# pcb_main.net
KiCad netlist of a schematic drawn in EAGLE
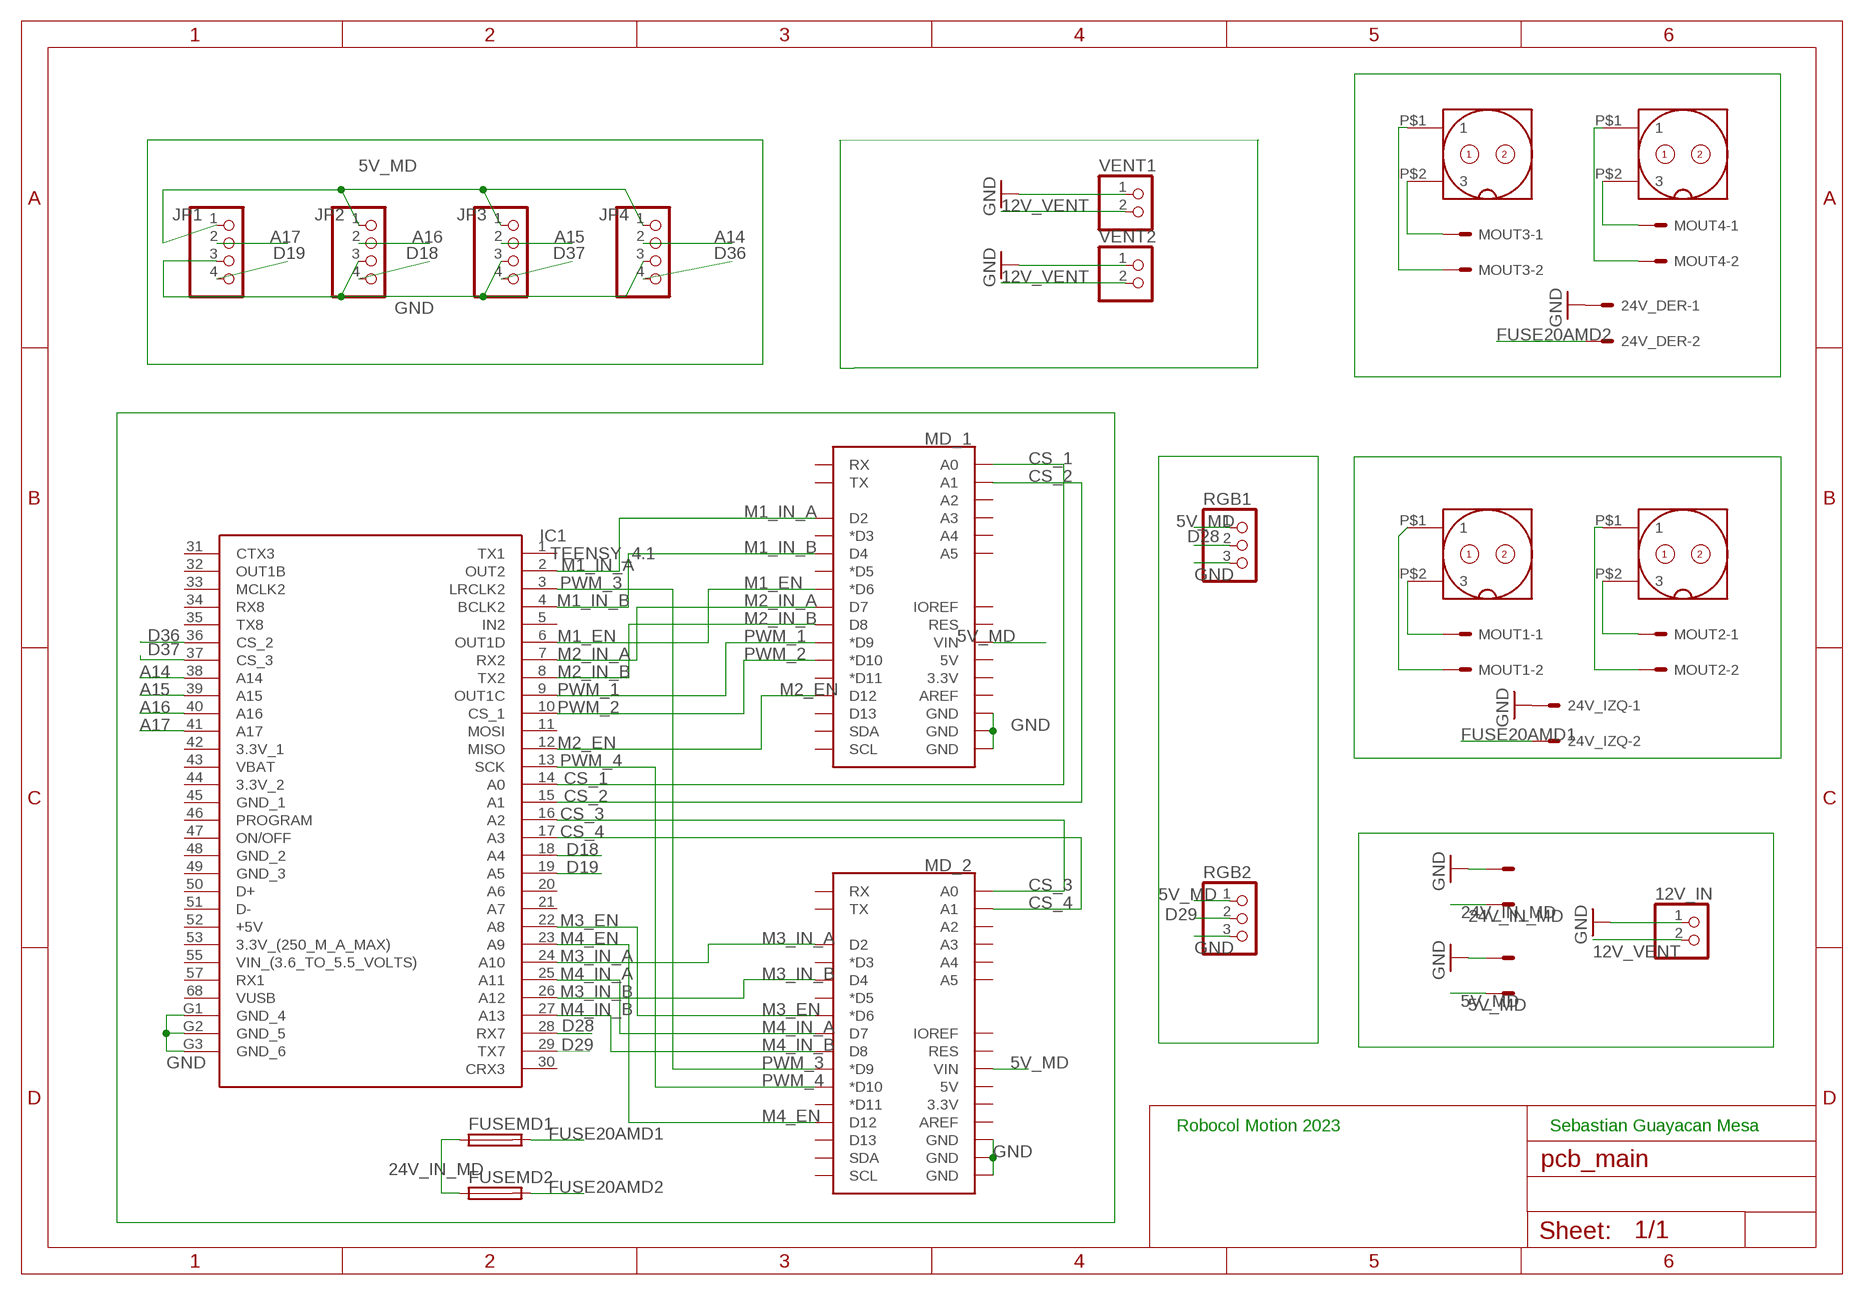
[diagram p0: schematic, sheet 1]

(export (version "E")
  (design (tool "Eeschema 10.0.6"))
  (components
    (comp (ref "5_MD")
      (value "5566-25569-2")
      (footprint "eagle-import:5569-2")
      (libsource (lib "eagle-import") (part "5566-25569-2"))
    )
    (comp (ref "12V_IN")
      (value "PINHD-1X2")
      (footprint "eagle-import:1X02")
      (libsource (lib "eagle-import") (part "PINHD-1X2"))
    )
    (comp (ref "24V_DER")
      (value "5566-25569-2")
      (footprint "eagle-import:5569-2")
      (libsource (lib "eagle-import") (part "5566-25569-2"))
    )
    (comp (ref "24V_IZQ")
      (value "5566-25569-2")
      (footprint "eagle-import:5569-2")
      (libsource (lib "eagle-import") (part "5566-25569-2"))
    )
    (comp (ref "24V_MD")
      (value "5566-25569-2")
      (footprint "eagle-import:5569-2")
      (libsource (lib "eagle-import") (part "5566-25569-2"))
    )
    (comp (ref "FUSEMD1")
      (value "FUSEBLANK_5X20MM")
      (footprint "eagle-import:FUSE_HOLDER_5X20MM")
      (libsource (lib "eagle-import") (part "FUSEBLANK_5X20MM"))
    )
    (comp (ref "FUSEMD2")
      (value "FUSEBLANK_5X20MM")
      (footprint "eagle-import:FUSE_HOLDER_5X20MM")
      (libsource (lib "eagle-import") (part "FUSEBLANK_5X20MM"))
    )
    (comp (ref "IC1")
      (value "TEENSY_4.1")
      (footprint "eagle-import:TEENSY41")
      (fields (field (name "MANUFACTURER_PART_NUMBER") "TEENSY 4.1"))
      (libsource (lib "eagle-import") (part "TEENSY_4.1"))
    )
    (comp (ref "JP1")
      (value "PINHD-1X4")
      (footprint "eagle-import:1X04")
      (libsource (lib "eagle-import") (part "PINHD-1X4"))
    )
    (comp (ref "JP2")
      (value "PINHD-1X4")
      (footprint "eagle-import:1X04")
      (libsource (lib "eagle-import") (part "PINHD-1X4"))
    )
    (comp (ref "JP3")
      (value "PINHD-1X4")
      (footprint "eagle-import:1X04")
      (libsource (lib "eagle-import") (part "PINHD-1X4"))
    )
    (comp (ref "JP4")
      (value "PINHD-1X4")
      (footprint "eagle-import:1X04")
      (libsource (lib "eagle-import") (part "PINHD-1X4"))
    )
    (comp (ref "M1")
      (value "GX16_2_PINS")
      (footprint "eagle-import:GX16_2_PINS_PADS")
      (libsource (lib "eagle-import") (part "GX16_2_PINS"))
    )
    (comp (ref "M2")
      (value "GX16_2_PINS")
      (footprint "eagle-import:GX16_2_PINS_PADS")
      (libsource (lib "eagle-import") (part "GX16_2_PINS"))
    )
    (comp (ref "M3")
      (value "GX16_2_PINS")
      (footprint "eagle-import:GX16_2_PINS_PADS")
      (libsource (lib "eagle-import") (part "GX16_2_PINS"))
    )
    (comp (ref "M4")
      (value "GX16_2_PINS")
      (footprint "eagle-import:GX16_2_PINS_PADS")
      (libsource (lib "eagle-import") (part "GX16_2_PINS"))
    )
    (comp (ref "MD_1")
      (value "ARDUINO_UNO_R3_SHIELDBASIC")
      (footprint "eagle-import:UNO_R3_SHIELD")
      (libsource (lib "eagle-import") (part "ARDUINO_UNO_R3_SHIELDBASIC"))
    )
    (comp (ref "MD_2")
      (value "ARDUINO_UNO_R3_SHIELDBASIC")
      (footprint "eagle-import:UNO_R3_SHIELD")
      (libsource (lib "eagle-import") (part "ARDUINO_UNO_R3_SHIELDBASIC"))
    )
    (comp (ref "MOUT1")
      (value "5566-25569-2")
      (footprint "eagle-import:5569-2")
      (libsource (lib "eagle-import") (part "5566-25569-2"))
    )
    (comp (ref "MOUT2")
      (value "5566-25569-2")
      (footprint "eagle-import:5569-2")
      (libsource (lib "eagle-import") (part "5566-25569-2"))
    )
    (comp (ref "MOUT3")
      (value "5566-25569-2")
      (footprint "eagle-import:5569-2")
      (libsource (lib "eagle-import") (part "5566-25569-2"))
    )
    (comp (ref "MOUT4")
      (value "5566-25569-2")
      (footprint "eagle-import:5569-2")
      (libsource (lib "eagle-import") (part "5566-25569-2"))
    )
    (comp (ref "RGB1")
      (value "PINHD-1X3")
      (footprint "eagle-import:1X03")
      (libsource (lib "eagle-import") (part "PINHD-1X3"))
    )
    (comp (ref "RGB2")
      (value "PINHD-1X3")
      (footprint "eagle-import:1X03")
      (libsource (lib "eagle-import") (part "PINHD-1X3"))
    )
    (comp (ref "VENT1")
      (value "PINHD-1X2")
      (footprint "eagle-import:1X02")
      (libsource (lib "eagle-import") (part "PINHD-1X2"))
    )
    (comp (ref "VENT2")
      (value "PINHD-1X2")
      (footprint "eagle-import:1X02")
      (libsource (lib "eagle-import") (part "PINHD-1X2"))
    )
  )
  (nets
    (net (code "1") (name "/5V_MD") (class "Default")
      (node (ref "5_MD") (pin "2") (pinfunction "S_2") (pintype "passive"))
      (node (ref "JP1") (pin "1") (pinfunction "1_1") (pintype "passive"))
      (node (ref "JP2") (pin "1") (pinfunction "1_1") (pintype "passive"))
      (node (ref "JP3") (pin "1") (pinfunction "1_1") (pintype "passive"))
      (node (ref "JP4") (pin "1") (pinfunction "1_1") (pintype "passive"))
      (node (ref "MD_1") (pin "VIN") (pinfunction "VIN_VIN") (pintype "bidirectional"))
      (node (ref "MD_2") (pin "VIN") (pinfunction "VIN_VIN") (pintype "bidirectional"))
      (node (ref "RGB1") (pin "1") (pinfunction "1_1") (pintype "passive"))
      (node (ref "RGB2") (pin "1") (pinfunction "1_1") (pintype "passive"))
    )
    (net (code "2") (name "/12V_VENT") (class "Default")
      (node (ref "12V_IN") (pin "2") (pinfunction "2_2") (pintype "passive"))
      (node (ref "VENT1") (pin "2") (pinfunction "2_2") (pintype "passive"))
      (node (ref "VENT2") (pin "2") (pinfunction "2_2") (pintype "passive"))
    )
    (net (code "3") (name "/24V_IN_MD") (class "Default")
      (node (ref "24V_MD") (pin "2") (pinfunction "S_2") (pintype "passive"))
      (node (ref "FUSEMD1") (pin "1") (pinfunction "1_1") (pintype "passive"))
      (node (ref "FUSEMD2") (pin "1") (pinfunction "1_1") (pintype "passive"))
    )
    (net (code "4") (name "/A14") (class "Default")
      (node (ref "IC1") (pin "38") (pinfunction "A14_38") (pintype "bidirectional"))
      (node (ref "JP4") (pin "2") (pinfunction "2_2") (pintype "passive"))
    )
    (net (code "5") (name "/A15") (class "Default")
      (node (ref "IC1") (pin "39") (pinfunction "A15_39") (pintype "bidirectional"))
      (node (ref "JP3") (pin "2") (pinfunction "2_2") (pintype "passive"))
    )
    (net (code "6") (name "/A16") (class "Default")
      (node (ref "IC1") (pin "40") (pinfunction "A16_40") (pintype "bidirectional"))
      (node (ref "JP2") (pin "2") (pinfunction "2_2") (pintype "passive"))
    )
    (net (code "7") (name "/A17") (class "Default")
      (node (ref "IC1") (pin "41") (pinfunction "A17_41") (pintype "bidirectional"))
      (node (ref "JP1") (pin "2") (pinfunction "2_2") (pintype "passive"))
    )
    (net (code "8") (name "/CS_1") (class "Default")
      (node (ref "IC1") (pin "14") (pinfunction "A0_14") (pintype "bidirectional"))
      (node (ref "MD_1") (pin "A0") (pinfunction "A0_A0") (pintype "bidirectional"))
    )
    (net (code "9") (name "/CS_2") (class "Default")
      (node (ref "IC1") (pin "15") (pinfunction "A1_15") (pintype "bidirectional"))
      (node (ref "MD_1") (pin "A1") (pinfunction "A1_A1") (pintype "bidirectional"))
    )
    (net (code "10") (name "/CS_3") (class "Default")
      (node (ref "IC1") (pin "16") (pinfunction "A2_16") (pintype "bidirectional"))
      (node (ref "MD_2") (pin "A0") (pinfunction "A0_A0") (pintype "bidirectional"))
    )
    (net (code "11") (name "/CS_4") (class "Default")
      (node (ref "IC1") (pin "17") (pinfunction "A3_17") (pintype "bidirectional"))
      (node (ref "MD_2") (pin "A1") (pinfunction "A1_A1") (pintype "bidirectional"))
    )
    (net (code "12") (name "/D18") (class "Default")
      (node (ref "IC1") (pin "18") (pinfunction "A4_18") (pintype "bidirectional"))
      (node (ref "JP2") (pin "4") (pinfunction "4_4") (pintype "passive"))
    )
    (net (code "13") (name "/D19") (class "Default")
      (node (ref "IC1") (pin "19") (pinfunction "A5_19") (pintype "bidirectional"))
      (node (ref "JP1") (pin "4") (pinfunction "4_4") (pintype "passive"))
    )
    (net (code "14") (name "/D28") (class "Default")
      (node (ref "IC1") (pin "28") (pinfunction "RX7_28") (pintype "bidirectional"))
      (node (ref "RGB1") (pin "2") (pinfunction "2_2") (pintype "passive"))
    )
    (net (code "15") (name "/D29") (class "Default")
      (node (ref "IC1") (pin "29") (pinfunction "TX7_29") (pintype "bidirectional"))
      (node (ref "RGB2") (pin "2") (pinfunction "2_2") (pintype "passive"))
    )
    (net (code "16") (name "/D36") (class "Default")
      (node (ref "IC1") (pin "36") (pinfunction "CS_2_36") (pintype "bidirectional"))
      (node (ref "JP4") (pin "4") (pinfunction "4_4") (pintype "passive"))
    )
    (net (code "17") (name "/D37") (class "Default")
      (node (ref "IC1") (pin "37") (pinfunction "CS_3_37") (pintype "bidirectional"))
      (node (ref "JP3") (pin "4") (pinfunction "4_4") (pintype "passive"))
    )
    (net (code "18") (name "/FUSE20AMD1") (class "Default")
      (node (ref "24V_IZQ") (pin "2") (pinfunction "S_2") (pintype "passive"))
      (node (ref "FUSEMD1") (pin "2") (pinfunction "2_2") (pintype "passive"))
    )
    (net (code "19") (name "/FUSE20AMD2") (class "Default")
      (node (ref "24V_DER") (pin "2") (pinfunction "S_2") (pintype "passive"))
      (node (ref "FUSEMD2") (pin "2") (pinfunction "2_2") (pintype "passive"))
    )
    (net (code "20") (name "/M1_EN") (class "Default")
      (node (ref "IC1") (pin "6") (pinfunction "OUT1D_6") (pintype "bidirectional"))
      (node (ref "MD_1") (pin "D6") (pinfunction "*D6_D6") (pintype "bidirectional"))
    )
    (net (code "21") (name "/M1_IN_A") (class "Default")
      (node (ref "IC1") (pin "2") (pinfunction "OUT2_2") (pintype "bidirectional"))
      (node (ref "MD_1") (pin "D2") (pinfunction "D2_D2") (pintype "bidirectional"))
    )
    (net (code "22") (name "/M1_IN_B") (class "Default")
      (node (ref "IC1") (pin "4") (pinfunction "BCLK2_4") (pintype "bidirectional"))
      (node (ref "MD_1") (pin "D4") (pinfunction "D4_D4") (pintype "bidirectional"))
    )
    (net (code "23") (name "/M2_EN") (class "Default")
      (node (ref "IC1") (pin "12") (pinfunction "MISO_12") (pintype "bidirectional"))
      (node (ref "MD_1") (pin "D12") (pinfunction "D12_D12") (pintype "bidirectional"))
    )
    (net (code "24") (name "/M2_IN_A") (class "Default")
      (node (ref "IC1") (pin "7") (pinfunction "RX2_7") (pintype "bidirectional"))
      (node (ref "MD_1") (pin "D7") (pinfunction "D7_D7") (pintype "bidirectional"))
    )
    (net (code "25") (name "/M2_IN_B") (class "Default")
      (node (ref "IC1") (pin "8") (pinfunction "TX2_8") (pintype "bidirectional"))
      (node (ref "MD_1") (pin "D8") (pinfunction "D8_D8") (pintype "bidirectional"))
    )
    (net (code "26") (name "/M3_EN") (class "Default")
      (node (ref "IC1") (pin "22") (pinfunction "A8_22") (pintype "bidirectional"))
      (node (ref "MD_2") (pin "D6") (pinfunction "*D6_D6") (pintype "bidirectional"))
    )
    (net (code "27") (name "/M3_IN_A") (class "Default")
      (node (ref "IC1") (pin "24") (pinfunction "A10_24") (pintype "bidirectional"))
      (node (ref "MD_2") (pin "D2") (pinfunction "D2_D2") (pintype "bidirectional"))
    )
    (net (code "28") (name "/M3_IN_B") (class "Default")
      (node (ref "IC1") (pin "26") (pinfunction "A12_26") (pintype "bidirectional"))
      (node (ref "MD_2") (pin "D4") (pinfunction "D4_D4") (pintype "bidirectional"))
    )
    (net (code "29") (name "/M4_EN") (class "Default")
      (node (ref "IC1") (pin "23") (pinfunction "A9_23") (pintype "bidirectional"))
      (node (ref "MD_2") (pin "D12") (pinfunction "D12_D12") (pintype "bidirectional"))
    )
    (net (code "30") (name "/M4_IN_A") (class "Default")
      (node (ref "IC1") (pin "25") (pinfunction "A11_25") (pintype "bidirectional"))
      (node (ref "MD_2") (pin "D7") (pinfunction "D7_D7") (pintype "bidirectional"))
    )
    (net (code "31") (name "/M4_IN_B") (class "Default")
      (node (ref "IC1") (pin "27") (pinfunction "A13_27") (pintype "bidirectional"))
      (node (ref "MD_2") (pin "D8") (pinfunction "D8_D8") (pintype "bidirectional"))
    )
    (net (code "32") (name "/PWM_1") (class "Default")
      (node (ref "IC1") (pin "9") (pinfunction "OUT1C_9") (pintype "bidirectional"))
      (node (ref "MD_1") (pin "D9") (pinfunction "*D9_D9") (pintype "bidirectional"))
    )
    (net (code "33") (name "/PWM_2") (class "Default")
      (node (ref "IC1") (pin "10") (pinfunction "CS_1_10") (pintype "bidirectional"))
      (node (ref "MD_1") (pin "D10") (pinfunction "*D10_D10") (pintype "bidirectional"))
    )
    (net (code "34") (name "/PWM_3") (class "Default")
      (node (ref "IC1") (pin "3") (pinfunction "LRCLK2_3") (pintype "bidirectional"))
      (node (ref "MD_2") (pin "D9") (pinfunction "*D9_D9") (pintype "bidirectional"))
    )
    (net (code "35") (name "/PWM_4") (class "Default")
      (node (ref "IC1") (pin "13") (pinfunction "SCK_13") (pintype "bidirectional"))
      (node (ref "MD_2") (pin "D10") (pinfunction "*D10_D10") (pintype "bidirectional"))
    )
    (net (code "36") (name "GND") (class "Default")
      (node (ref "12V_IN") (pin "1") (pinfunction "1_1") (pintype "passive"))
      (node (ref "24V_DER") (pin "1") (pinfunction "S_1") (pintype "passive"))
      (node (ref "24V_IZQ") (pin "1") (pinfunction "S_1") (pintype "passive"))
      (node (ref "24V_MD") (pin "1") (pinfunction "S_1") (pintype "passive"))
      (node (ref "5_MD") (pin "1") (pinfunction "S_1") (pintype "passive"))
      (node (ref "IC1") (pin "G1") (pinfunction "GND_4_G1") (pintype "bidirectional"))
      (node (ref "IC1") (pin "G2") (pinfunction "GND_5_G2") (pintype "bidirectional"))
      (node (ref "IC1") (pin "G3") (pinfunction "GND_6_G3") (pintype "bidirectional"))
      (node (ref "JP1") (pin "3") (pinfunction "3_3") (pintype "passive"))
      (node (ref "JP2") (pin "3") (pinfunction "3_3") (pintype "passive"))
      (node (ref "JP3") (pin "3") (pinfunction "3_3") (pintype "passive"))
      (node (ref "JP4") (pin "3") (pinfunction "3_3") (pintype "passive"))
      (node (ref "MD_1") (pin "GND@0") (pinfunction "GND_GND@0") (pintype "bidirectional"))
      (node (ref "MD_1") (pin "GND@1") (pinfunction "GND_GND@1") (pintype "bidirectional"))
      (node (ref "MD_1") (pin "GND@2") (pinfunction "GND_GND@2") (pintype "bidirectional"))
      (node (ref "MD_2") (pin "GND@0") (pinfunction "GND_GND@0") (pintype "bidirectional"))
      (node (ref "MD_2") (pin "GND@1") (pinfunction "GND_GND@1") (pintype "bidirectional"))
      (node (ref "MD_2") (pin "GND@2") (pinfunction "GND_GND@2") (pintype "bidirectional"))
      (node (ref "RGB1") (pin "3") (pinfunction "3_3") (pintype "passive"))
      (node (ref "RGB2") (pin "3") (pinfunction "3_3") (pintype "passive"))
      (node (ref "VENT1") (pin "1") (pinfunction "1_1") (pintype "passive"))
      (node (ref "VENT2") (pin "1") (pinfunction "1_1") (pintype "passive"))
    )
    (net (code "37") (name "Net-(M1-1)") (class "Default")
      (node (ref "M1") (pin "P$1") (pinfunction "1_P$1") (pintype "bidirectional"))
      (node (ref "MOUT1") (pin "2") (pinfunction "S_2") (pintype "passive"))
    )
    (net (code "38") (name "Net-(M1-3)") (class "Default")
      (node (ref "M1") (pin "P$2") (pinfunction "3_P$2") (pintype "bidirectional"))
      (node (ref "MOUT1") (pin "1") (pinfunction "S_1") (pintype "passive"))
    )
    (net (code "39") (name "Net-(M2-1)") (class "Default")
      (node (ref "M2") (pin "P$1") (pinfunction "1_P$1") (pintype "bidirectional"))
      (node (ref "MOUT2") (pin "2") (pinfunction "S_2") (pintype "passive"))
    )
    (net (code "40") (name "Net-(M2-3)") (class "Default")
      (node (ref "M2") (pin "P$2") (pinfunction "3_P$2") (pintype "bidirectional"))
      (node (ref "MOUT2") (pin "1") (pinfunction "S_1") (pintype "passive"))
    )
    (net (code "41") (name "Net-(M3-1)") (class "Default")
      (node (ref "M3") (pin "P$1") (pinfunction "1_P$1") (pintype "bidirectional"))
      (node (ref "MOUT3") (pin "2") (pinfunction "S_2") (pintype "passive"))
    )
    (net (code "42") (name "Net-(M3-3)") (class "Default")
      (node (ref "M3") (pin "P$2") (pinfunction "3_P$2") (pintype "bidirectional"))
      (node (ref "MOUT3") (pin "1") (pinfunction "S_1") (pintype "passive"))
    )
    (net (code "43") (name "Net-(M4-1)") (class "Default")
      (node (ref "M4") (pin "P$1") (pinfunction "1_P$1") (pintype "bidirectional"))
      (node (ref "MOUT4") (pin "2") (pinfunction "S_2") (pintype "passive"))
    )
    (net (code "44") (name "Net-(M4-3)") (class "Default")
      (node (ref "M4") (pin "P$2") (pinfunction "3_P$2") (pintype "bidirectional"))
      (node (ref "MOUT4") (pin "1") (pinfunction "S_1") (pintype "passive"))
    )
    (net (code "45") (name "unconnected-(IC1-+5V-Pad52)") (class "Default")
      (node (ref "IC1") (pin "52") (pinfunction "+5V_52") (pintype "bidirectional"))
    )
    (net (code "46") (name "unconnected-(IC1-3.3V_(250_M_A_MAX)-Pad53)") (class "Default")
      (node (ref "IC1") (pin "53") (pinfunction "3.3V_(250_M_A_MAX)_53") (pintype "bidirectional"))
    )
    (net (code "47") (name "unconnected-(IC1-3.3V_1-Pad42)") (class "Default")
      (node (ref "IC1") (pin "42") (pinfunction "3.3V_1_42") (pintype "bidirectional"))
    )
    (net (code "48") (name "unconnected-(IC1-3.3V_2-Pad44)") (class "Default")
      (node (ref "IC1") (pin "44") (pinfunction "3.3V_2_44") (pintype "bidirectional"))
    )
    (net (code "49") (name "unconnected-(IC1-A6-Pad20)") (class "Default")
      (node (ref "IC1") (pin "20") (pinfunction "A6_20") (pintype "bidirectional"))
    )
    (net (code "50") (name "unconnected-(IC1-A7-Pad21)") (class "Default")
      (node (ref "IC1") (pin "21") (pinfunction "A7_21") (pintype "bidirectional"))
    )
    (net (code "51") (name "unconnected-(IC1-CRX3-Pad30)") (class "Default")
      (node (ref "IC1") (pin "30") (pinfunction "CRX3_30") (pintype "bidirectional"))
    )
    (net (code "52") (name "unconnected-(IC1-CTX3-Pad31)") (class "Default")
      (node (ref "IC1") (pin "31") (pinfunction "CTX3_31") (pintype "bidirectional"))
    )
    (net (code "53") (name "unconnected-(IC1-D+-Pad50)") (class "Default")
      (node (ref "IC1") (pin "50") (pinfunction "D+_50") (pintype "bidirectional"))
    )
    (net (code "54") (name "unconnected-(IC1-D--Pad51)") (class "Default")
      (node (ref "IC1") (pin "51") (pinfunction "D-_51") (pintype "bidirectional"))
    )
    (net (code "55") (name "unconnected-(IC1-GND_1-Pad45)") (class "Default")
      (node (ref "IC1") (pin "45") (pinfunction "GND_1_45") (pintype "bidirectional"))
    )
    (net (code "56") (name "unconnected-(IC1-GND_2-Pad48)") (class "Default")
      (node (ref "IC1") (pin "48") (pinfunction "GND_2_48") (pintype "bidirectional"))
    )
    (net (code "57") (name "unconnected-(IC1-GND_3-Pad49)") (class "Default")
      (node (ref "IC1") (pin "49") (pinfunction "GND_3_49") (pintype "bidirectional"))
    )
    (net (code "58") (name "unconnected-(IC1-IN2-Pad5)") (class "Default")
      (node (ref "IC1") (pin "5") (pinfunction "IN2_5") (pintype "bidirectional"))
    )
    (net (code "59") (name "unconnected-(IC1-MCLK2-Pad33)") (class "Default")
      (node (ref "IC1") (pin "33") (pinfunction "MCLK2_33") (pintype "bidirectional"))
    )
    (net (code "60") (name "unconnected-(IC1-MOSI-Pad11)") (class "Default")
      (node (ref "IC1") (pin "11") (pinfunction "MOSI_11") (pintype "bidirectional"))
    )
    (net (code "61") (name "unconnected-(IC1-ON{slash}OFF-Pad47)") (class "Default")
      (node (ref "IC1") (pin "47") (pinfunction "ON/OFF_47") (pintype "bidirectional"))
    )
    (net (code "62") (name "unconnected-(IC1-OUT1B-Pad32)") (class "Default")
      (node (ref "IC1") (pin "32") (pinfunction "OUT1B_32") (pintype "bidirectional"))
    )
    (net (code "63") (name "unconnected-(IC1-PROGRAM-Pad46)") (class "Default")
      (node (ref "IC1") (pin "46") (pinfunction "PROGRAM_46") (pintype "bidirectional"))
    )
    (net (code "64") (name "unconnected-(IC1-RX1-Pad57)") (class "Default")
      (node (ref "IC1") (pin "57") (pinfunction "RX1_57") (pintype "bidirectional"))
    )
    (net (code "65") (name "unconnected-(IC1-RX8-Pad34)") (class "Default")
      (node (ref "IC1") (pin "34") (pinfunction "RX8_34") (pintype "bidirectional"))
    )
    (net (code "66") (name "unconnected-(IC1-TX1-Pad1)") (class "Default")
      (node (ref "IC1") (pin "1") (pinfunction "TX1_1") (pintype "bidirectional"))
    )
    (net (code "67") (name "unconnected-(IC1-TX8-Pad35)") (class "Default")
      (node (ref "IC1") (pin "35") (pinfunction "TX8_35") (pintype "bidirectional"))
    )
    (net (code "68") (name "unconnected-(IC1-VBAT-Pad43)") (class "Default")
      (node (ref "IC1") (pin "43") (pinfunction "VBAT_43") (pintype "bidirectional"))
    )
    (net (code "69") (name "unconnected-(IC1-VIN_(3.6_TO_5.5_VOLTS)-Pad55)") (class "Default")
      (node (ref "IC1") (pin "55") (pinfunction "VIN_(3.6_TO_5.5_VOLTS)_55") (pintype "bidirectional"))
    )
    (net (code "70") (name "unconnected-(IC1-VUSB-Pad68)") (class "Default")
      (node (ref "IC1") (pin "68") (pinfunction "VUSB_68") (pintype "bidirectional"))
    )
    (net (code "71") (name "unconnected-(MD_1-*D3-PadD3)") (class "Default")
      (node (ref "MD_1") (pin "D3") (pinfunction "*D3_D3") (pintype "bidirectional"))
    )
    (net (code "72") (name "unconnected-(MD_1-*D5-PadD5)") (class "Default")
      (node (ref "MD_1") (pin "D5") (pinfunction "*D5_D5") (pintype "bidirectional"))
    )
    (net (code "73") (name "unconnected-(MD_1-*D11-PadD11)") (class "Default")
      (node (ref "MD_1") (pin "D11") (pinfunction "*D11_D11") (pintype "bidirectional"))
    )
    (net (code "74") (name "unconnected-(MD_1-Pad3.3V)") (class "Default")
      (node (ref "MD_1") (pin "3.3V") (pinfunction "3.3V_3.3V") (pintype "bidirectional"))
    )
    (net (code "75") (name "unconnected-(MD_1-Pad5V)") (class "Default")
      (node (ref "MD_1") (pin "5V") (pinfunction "5V_5V") (pintype "bidirectional"))
    )
    (net (code "76") (name "unconnected-(MD_1-PadA2)") (class "Default")
      (node (ref "MD_1") (pin "A2") (pinfunction "A2_A2") (pintype "bidirectional"))
    )
    (net (code "77") (name "unconnected-(MD_1-PadA3)") (class "Default")
      (node (ref "MD_1") (pin "A3") (pinfunction "A3_A3") (pintype "bidirectional"))
    )
    (net (code "78") (name "unconnected-(MD_1-PadA4)") (class "Default")
      (node (ref "MD_1") (pin "A4") (pinfunction "A4_A4") (pintype "bidirectional"))
    )
    (net (code "79") (name "unconnected-(MD_1-PadA5)") (class "Default")
      (node (ref "MD_1") (pin "A5") (pinfunction "A5_A5") (pintype "bidirectional"))
    )
    (net (code "80") (name "unconnected-(MD_1-PadAREF)") (class "Default")
      (node (ref "MD_1") (pin "AREF") (pinfunction "AREF_AREF") (pintype "bidirectional"))
    )
    (net (code "81") (name "unconnected-(MD_1-PadD13)") (class "Default")
      (node (ref "MD_1") (pin "D13") (pinfunction "D13_D13") (pintype "bidirectional"))
    )
    (net (code "82") (name "unconnected-(MD_1-PadIOREF)") (class "Default")
      (node (ref "MD_1") (pin "IOREF") (pinfunction "IOREF_IOREF") (pintype "bidirectional"))
    )
    (net (code "83") (name "unconnected-(MD_1-PadRES)") (class "Default")
      (node (ref "MD_1") (pin "RES") (pinfunction "RES_RES") (pintype "bidirectional"))
    )
    (net (code "84") (name "unconnected-(MD_1-PadRX)") (class "Default")
      (node (ref "MD_1") (pin "RX") (pinfunction "RX_RX") (pintype "bidirectional"))
    )
    (net (code "85") (name "unconnected-(MD_1-PadSCL)") (class "Default")
      (node (ref "MD_1") (pin "SCL") (pinfunction "SCL_SCL") (pintype "bidirectional"))
    )
    (net (code "86") (name "unconnected-(MD_1-PadSDA)") (class "Default")
      (node (ref "MD_1") (pin "SDA") (pinfunction "SDA_SDA") (pintype "bidirectional"))
    )
    (net (code "87") (name "unconnected-(MD_1-PadTX)") (class "Default")
      (node (ref "MD_1") (pin "TX") (pinfunction "TX_TX") (pintype "bidirectional"))
    )
    (net (code "88") (name "unconnected-(MD_2-*D3-PadD3)") (class "Default")
      (node (ref "MD_2") (pin "D3") (pinfunction "*D3_D3") (pintype "bidirectional"))
    )
    (net (code "89") (name "unconnected-(MD_2-*D5-PadD5)") (class "Default")
      (node (ref "MD_2") (pin "D5") (pinfunction "*D5_D5") (pintype "bidirectional"))
    )
    (net (code "90") (name "unconnected-(MD_2-*D11-PadD11)") (class "Default")
      (node (ref "MD_2") (pin "D11") (pinfunction "*D11_D11") (pintype "bidirectional"))
    )
    (net (code "91") (name "unconnected-(MD_2-Pad3.3V)") (class "Default")
      (node (ref "MD_2") (pin "3.3V") (pinfunction "3.3V_3.3V") (pintype "bidirectional"))
    )
    (net (code "92") (name "unconnected-(MD_2-Pad5V)") (class "Default")
      (node (ref "MD_2") (pin "5V") (pinfunction "5V_5V") (pintype "bidirectional"))
    )
    (net (code "93") (name "unconnected-(MD_2-PadA2)") (class "Default")
      (node (ref "MD_2") (pin "A2") (pinfunction "A2_A2") (pintype "bidirectional"))
    )
    (net (code "94") (name "unconnected-(MD_2-PadA3)") (class "Default")
      (node (ref "MD_2") (pin "A3") (pinfunction "A3_A3") (pintype "bidirectional"))
    )
    (net (code "95") (name "unconnected-(MD_2-PadA4)") (class "Default")
      (node (ref "MD_2") (pin "A4") (pinfunction "A4_A4") (pintype "bidirectional"))
    )
    (net (code "96") (name "unconnected-(MD_2-PadA5)") (class "Default")
      (node (ref "MD_2") (pin "A5") (pinfunction "A5_A5") (pintype "bidirectional"))
    )
    (net (code "97") (name "unconnected-(MD_2-PadAREF)") (class "Default")
      (node (ref "MD_2") (pin "AREF") (pinfunction "AREF_AREF") (pintype "bidirectional"))
    )
    (net (code "98") (name "unconnected-(MD_2-PadD13)") (class "Default")
      (node (ref "MD_2") (pin "D13") (pinfunction "D13_D13") (pintype "bidirectional"))
    )
    (net (code "99") (name "unconnected-(MD_2-PadIOREF)") (class "Default")
      (node (ref "MD_2") (pin "IOREF") (pinfunction "IOREF_IOREF") (pintype "bidirectional"))
    )
    (net (code "100") (name "unconnected-(MD_2-PadRES)") (class "Default")
      (node (ref "MD_2") (pin "RES") (pinfunction "RES_RES") (pintype "bidirectional"))
    )
    (net (code "101") (name "unconnected-(MD_2-PadRX)") (class "Default")
      (node (ref "MD_2") (pin "RX") (pinfunction "RX_RX") (pintype "bidirectional"))
    )
    (net (code "102") (name "unconnected-(MD_2-PadSCL)") (class "Default")
      (node (ref "MD_2") (pin "SCL") (pinfunction "SCL_SCL") (pintype "bidirectional"))
    )
    (net (code "103") (name "unconnected-(MD_2-PadSDA)") (class "Default")
      (node (ref "MD_2") (pin "SDA") (pinfunction "SDA_SDA") (pintype "bidirectional"))
    )
    (net (code "104") (name "unconnected-(MD_2-PadTX)") (class "Default")
      (node (ref "MD_2") (pin "TX") (pinfunction "TX_TX") (pintype "bidirectional"))
    )
  )
)
